# RomeBoardV1.net
KiCad netlist of a schematic drawn in EAGLE
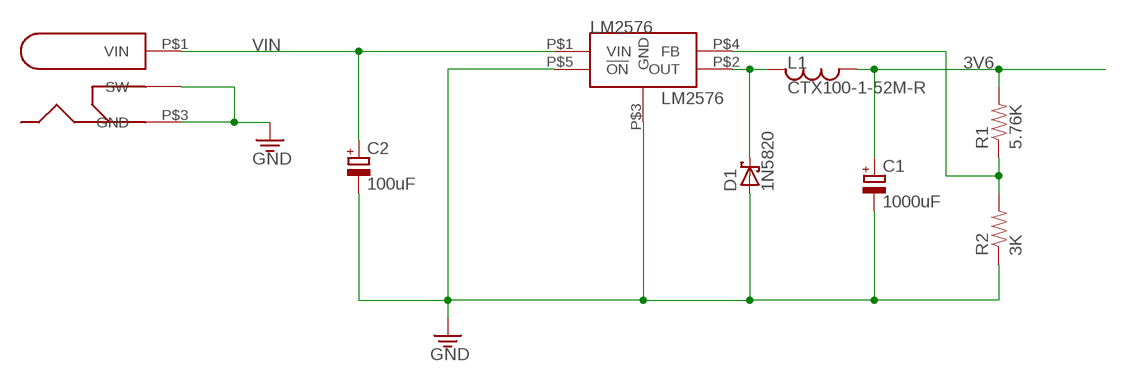
[diagram p0: schematic, sheet 1]
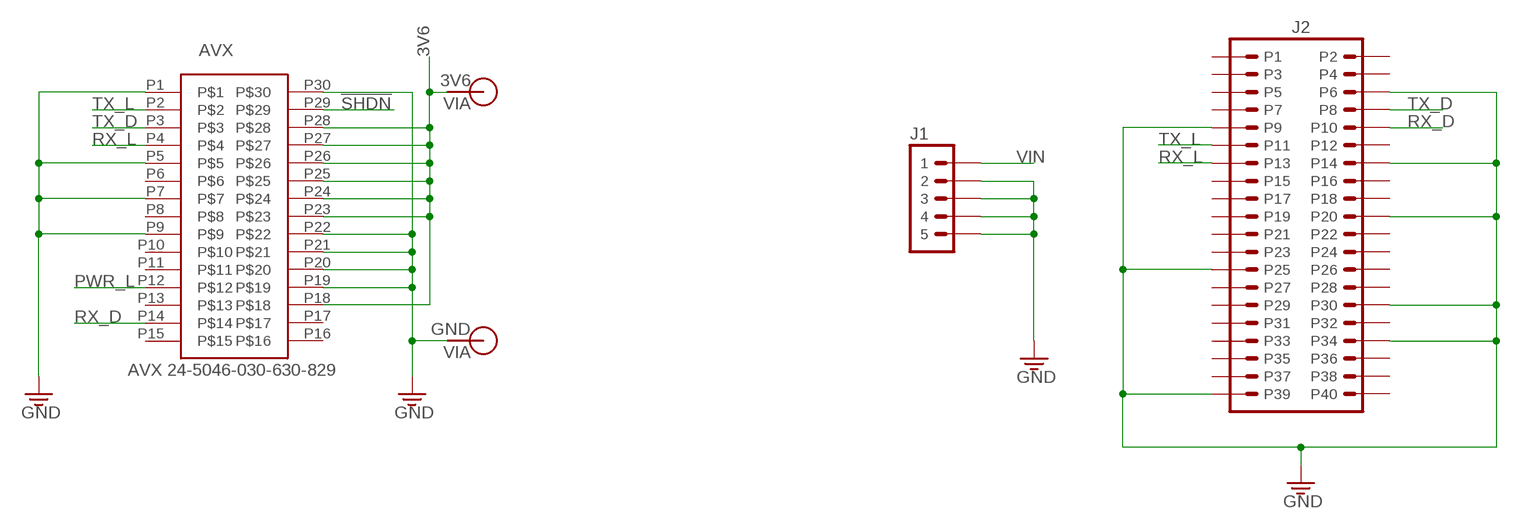
[diagram p1: schematic, sheet 2]
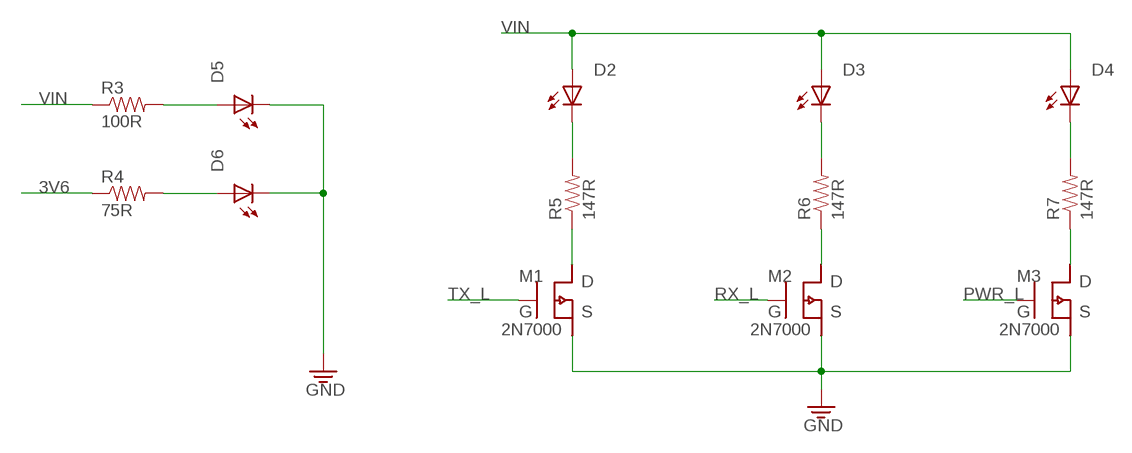
[diagram p2: schematic, sheet 3]

(export (version "E")
  (design (tool "Eeschema 10.0.6"))
  (components
    (comp (ref "AVX")
      (value "AVX-24-5046-030-630-829")
      (footprint "eagle-import:AVX-24-5046-630-829")
      (libsource (lib "eagle-import") (part "AVX-24-5046-030-630-829"))
    )
    (comp (ref "J1")
      (value "HEADER-5")
      (footprint "eagle-import:HEADER-05")
      (libsource (lib "eagle-import") (part "HEADER-5"))
    )
    (comp (ref "J2")
      (value "RASPBERRY-PI-HEADER")
      (footprint "eagle-import:HEADER-20X02")
      (libsource (lib "eagle-import") (part "RASPBERRY-PI-HEADER"))
    )
    (comp (ref "V4")
      (value "GND")
      (footprint "eagle-import:VIA-120MIL")
      (libsource (lib "eagle-import") (part "VIA-120MIL"))
    )
    (comp (ref "V5")
      (value "3V6")
      (footprint "eagle-import:VIA-120MIL")
      (libsource (lib "eagle-import") (part "VIA-120MIL"))
    )
    (comp (ref "D2")
      (value "LEDTHRU-HOLE-CONNECTOR")
      (footprint "eagle-import:1X2-POL")
      (libsource (lib "eagle-import") (part "LEDTHRU-HOLE-CONNECTOR"))
    )
    (comp (ref "D3")
      (value "LEDTHRU-HOLE-CONNECTOR")
      (footprint "eagle-import:1X2-POL")
      (libsource (lib "eagle-import") (part "LEDTHRU-HOLE-CONNECTOR"))
    )
    (comp (ref "D4")
      (value "LEDTHRU-HOLE-CONNECTOR")
      (footprint "eagle-import:1X2-POL")
      (libsource (lib "eagle-import") (part "LEDTHRU-HOLE-CONNECTOR"))
    )
    (comp (ref "D5")
      (value "LEDTHRU-HOLE-CONNECTOR")
      (footprint "eagle-import:1X2-POL")
      (libsource (lib "eagle-import") (part "LEDTHRU-HOLE-CONNECTOR"))
    )
    (comp (ref "D6")
      (value "LEDTHRU-HOLE-CONNECTOR")
      (footprint "eagle-import:1X2-POL")
      (libsource (lib "eagle-import") (part "LEDTHRU-HOLE-CONNECTOR"))
    )
    (comp (ref "M1")
      (value "2N7000")
      (footprint "eagle-import:TO-923-MOS")
      (libsource (lib "eagle-import") (part "2N7000"))
    )
    (comp (ref "M2")
      (value "2N7000")
      (footprint "eagle-import:TO-923-MOS")
      (libsource (lib "eagle-import") (part "2N7000"))
    )
    (comp (ref "M3")
      (value "2N7000")
      (footprint "eagle-import:TO-923-MOS")
      (libsource (lib "eagle-import") (part "2N7000"))
    )
    (comp (ref "R3")
      (value "100R")
      (footprint "eagle-import:AXIAL-0.4")
      (libsource (lib "eagle-import") (part "RESISTOR-PTH0.4"))
    )
    (comp (ref "R4")
      (value "75R")
      (footprint "eagle-import:AXIAL-0.4")
      (libsource (lib "eagle-import") (part "RESISTOR-PTH0.4"))
    )
    (comp (ref "R5")
      (value "147R")
      (footprint "eagle-import:AXIAL-0.4")
      (libsource (lib "eagle-import") (part "RESISTOR-PTH0.4"))
    )
    (comp (ref "R6")
      (value "147R")
      (footprint "eagle-import:AXIAL-0.4")
      (libsource (lib "eagle-import") (part "RESISTOR-PTH0.4"))
    )
    (comp (ref "R7")
      (value "147R")
      (footprint "eagle-import:AXIAL-0.4")
      (libsource (lib "eagle-import") (part "RESISTOR-PTH0.4"))
    )
    (comp (ref "C1")
      (value "1000uF")
      (footprint "eagle-import:E7,5-16")
      (libsource (lib "eagle-import") (part "CPOL-EUE7.5-16"))
    )
    (comp (ref "C2")
      (value "100uF")
      (footprint "eagle-import:E3,5-10")
      (libsource (lib "eagle-import") (part "CPOL-EUE3.5-10"))
    )
    (comp (ref "D1")
      (value "1N5820")
      (footprint "eagle-import:DO-201AD")
      (libsource (lib "eagle-import") (part "1N5820"))
    )
    (comp (ref "L1")
      (value "CTX100-1-52M-R")
      (footprint "eagle-import:CTX100-1-52M-R")
      (libsource (lib "eagle-import") (part "CTX100-1-52M-R"))
    )
    (comp (ref "LM2576")
      (value "LM2576")
      (footprint "eagle-import:TO-220-5")
      (libsource (lib "eagle-import") (part "LM2576"))
    )
    (comp (ref "R1")
      (value "5.76K")
      (footprint "eagle-import:AXIAL-0.4")
      (libsource (lib "eagle-import") (part "RESISTOR-PTH0.4"))
    )
    (comp (ref "R2")
      (value "3K")
      (footprint "eagle-import:AXIAL-0.4")
      (libsource (lib "eagle-import") (part "RESISTOR-PTH0.4"))
    )
    (comp (ref "U$2")
      (value "PJ-002A")
      (footprint "eagle-import:PJ-002A")
      (libsource (lib "eagle-import") (part "PJ-002A"))
    )
  )
  (nets
    (net (code "1") (name "3V6") (class "Default")
      (node (ref "AVX") (pin "P18") (pinfunction "P$18_P18") (pintype "bidirectional"))
      (node (ref "AVX") (pin "P23") (pinfunction "P$23_P23") (pintype "bidirectional"))
      (node (ref "AVX") (pin "P24") (pinfunction "P$24_P24") (pintype "bidirectional"))
      (node (ref "AVX") (pin "P25") (pinfunction "P$25_P25") (pintype "bidirectional"))
      (node (ref "AVX") (pin "P26") (pinfunction "P$26_P26") (pintype "bidirectional"))
      (node (ref "AVX") (pin "P27") (pinfunction "P$27_P27") (pintype "bidirectional"))
      (node (ref "AVX") (pin "P28") (pinfunction "P$28_P28") (pintype "bidirectional"))
      (node (ref "C1") (pin "+") (pinfunction "+_+") (pintype "passive"))
      (node (ref "L1") (pin "P$3") (pinfunction "P$2_P$3") (pintype "passive"))
      (node (ref "R1") (pin "2") (pinfunction "2_2") (pintype "passive"))
      (node (ref "R4") (pin "1") (pinfunction "1_1") (pintype "passive"))
      (node (ref "V5") (pin "P$1") (pinfunction "P$1_P$1") (pintype "bidirectional"))
    )
    (net (code "2") (name "GND") (class "Default")
      (node (ref "AVX") (pin "P1") (pinfunction "P$1_P1") (pintype "bidirectional"))
      (node (ref "AVX") (pin "P19") (pinfunction "P$19_P19") (pintype "bidirectional"))
      (node (ref "AVX") (pin "P20") (pinfunction "P$20_P20") (pintype "bidirectional"))
      (node (ref "AVX") (pin "P21") (pinfunction "P$21_P21") (pintype "bidirectional"))
      (node (ref "AVX") (pin "P22") (pinfunction "P$22_P22") (pintype "bidirectional"))
      (node (ref "AVX") (pin "P30") (pinfunction "P$30_P30") (pintype "bidirectional"))
      (node (ref "AVX") (pin "P5") (pinfunction "P$5_P5") (pintype "bidirectional"))
      (node (ref "AVX") (pin "P7") (pinfunction "P$7_P7") (pintype "bidirectional"))
      (node (ref "AVX") (pin "P9") (pinfunction "P$9_P9") (pintype "bidirectional"))
      (node (ref "C1") (pin "-") (pinfunction "-_-") (pintype "passive"))
      (node (ref "C2") (pin "-") (pinfunction "-_-") (pintype "passive"))
      (node (ref "D1") (pin "P$1") (pinfunction "A_P$1") (pintype "passive"))
      (node (ref "D5") (pin "2") (pinfunction "C_2") (pintype "passive"))
      (node (ref "D6") (pin "2") (pinfunction "C_2") (pintype "passive"))
      (node (ref "J1") (pin "2") (pinfunction "2_2") (pintype "passive"))
      (node (ref "J1") (pin "3") (pinfunction "3_3") (pintype "passive"))
      (node (ref "J1") (pin "4") (pinfunction "4_4") (pintype "passive"))
      (node (ref "J1") (pin "5") (pinfunction "5_5") (pintype "passive"))
      (node (ref "J2") (pin "P14") (pinfunction "P14_P14") (pintype "passive"))
      (node (ref "J2") (pin "P20") (pinfunction "P20_P20") (pintype "passive"))
      (node (ref "J2") (pin "P25") (pinfunction "P25_P25") (pintype "passive"))
      (node (ref "J2") (pin "P30") (pinfunction "P30_P30") (pintype "passive"))
      (node (ref "J2") (pin "P34") (pinfunction "P34_P34") (pintype "passive"))
      (node (ref "J2") (pin "P39") (pinfunction "P39_P39") (pintype "passive"))
      (node (ref "J2") (pin "P6") (pinfunction "P6_P6") (pintype "passive"))
      (node (ref "J2") (pin "P9") (pinfunction "P9_P9") (pintype "passive"))
      (node (ref "LM2576") (pin "P$3") (pinfunction "GND_P$3") (pintype "bidirectional"))
      (node (ref "LM2576") (pin "P$5") (pinfunction "~{ON}_P$5") (pintype "bidirectional"))
      (node (ref "M1") (pin "3") (pinfunction "S_3") (pintype "bidirectional"))
      (node (ref "M2") (pin "3") (pinfunction "S_3") (pintype "bidirectional"))
      (node (ref "M3") (pin "3") (pinfunction "S_3") (pintype "bidirectional"))
      (node (ref "R2") (pin "1") (pinfunction "1_1") (pintype "passive"))
      (node (ref "U$2") (pin "P$2") (pinfunction "SW_P$2") (pintype "bidirectional"))
      (node (ref "U$2") (pin "P$3") (pinfunction "GND_P$3") (pintype "bidirectional"))
      (node (ref "V4") (pin "P$1") (pinfunction "P$1_P$1") (pintype "bidirectional"))
    )
    (net (code "3") (name "Net-(D1-C)") (class "Default")
      (node (ref "D1") (pin "P$2") (pinfunction "C_P$2") (pintype "passive"))
      (node (ref "L1") (pin "P$1") (pinfunction "P$1_P$1") (pintype "passive"))
      (node (ref "LM2576") (pin "P$2") (pinfunction "OUT_P$2") (pintype "bidirectional"))
    )
    (net (code "4") (name "Net-(D2-C)") (class "Default")
      (node (ref "D2") (pin "2") (pinfunction "C_2") (pintype "passive"))
      (node (ref "R5") (pin "2") (pinfunction "2_2") (pintype "passive"))
    )
    (net (code "5") (name "Net-(D3-C)") (class "Default")
      (node (ref "D3") (pin "2") (pinfunction "C_2") (pintype "passive"))
      (node (ref "R6") (pin "2") (pinfunction "2_2") (pintype "passive"))
    )
    (net (code "6") (name "Net-(D4-C)") (class "Default")
      (node (ref "D4") (pin "2") (pinfunction "C_2") (pintype "passive"))
      (node (ref "R7") (pin "2") (pinfunction "2_2") (pintype "passive"))
    )
    (net (code "7") (name "Net-(D5-A)") (class "Default")
      (node (ref "D5") (pin "1") (pinfunction "A_1") (pintype "passive"))
      (node (ref "R3") (pin "2") (pinfunction "2_2") (pintype "passive"))
    )
    (net (code "8") (name "Net-(D6-A)") (class "Default")
      (node (ref "D6") (pin "1") (pinfunction "A_1") (pintype "passive"))
      (node (ref "R4") (pin "2") (pinfunction "2_2") (pintype "passive"))
    )
    (net (code "9") (name "Net-(LM2576-FB)") (class "Default")
      (node (ref "LM2576") (pin "P$4") (pinfunction "FB_P$4") (pintype "bidirectional"))
      (node (ref "R1") (pin "1") (pinfunction "1_1") (pintype "passive"))
      (node (ref "R2") (pin "2") (pinfunction "2_2") (pintype "passive"))
    )
    (net (code "10") (name "Net-(M1-D)") (class "Default")
      (node (ref "M1") (pin "1") (pinfunction "D_1") (pintype "bidirectional"))
      (node (ref "R5") (pin "1") (pinfunction "1_1") (pintype "passive"))
    )
    (net (code "11") (name "Net-(M2-D)") (class "Default")
      (node (ref "M2") (pin "1") (pinfunction "D_1") (pintype "bidirectional"))
      (node (ref "R6") (pin "1") (pinfunction "1_1") (pintype "passive"))
    )
    (net (code "12") (name "Net-(M3-D)") (class "Default")
      (node (ref "M3") (pin "1") (pinfunction "D_1") (pintype "bidirectional"))
      (node (ref "R7") (pin "1") (pinfunction "1_1") (pintype "passive"))
    )
    (net (code "13") (name "PWR_L") (class "Default")
      (node (ref "AVX") (pin "P12") (pinfunction "P$12_P12") (pintype "bidirectional"))
      (node (ref "M3") (pin "2") (pinfunction "G_2") (pintype "bidirectional"))
    )
    (net (code "14") (name "RX_D") (class "Default")
      (node (ref "AVX") (pin "P14") (pinfunction "P$14_P14") (pintype "bidirectional"))
      (node (ref "J2") (pin "P10") (pinfunction "P10_P10") (pintype "passive"))
    )
    (net (code "15") (name "RX_L") (class "Default")
      (node (ref "AVX") (pin "P4") (pinfunction "P$4_P4") (pintype "bidirectional"))
      (node (ref "J2") (pin "P13") (pinfunction "P13_P13") (pintype "passive"))
      (node (ref "M2") (pin "2") (pinfunction "G_2") (pintype "bidirectional"))
    )
    (net (code "16") (name "TX_D") (class "Default")
      (node (ref "AVX") (pin "P3") (pinfunction "P$3_P3") (pintype "bidirectional"))
      (node (ref "J2") (pin "P8") (pinfunction "P8_P8") (pintype "passive"))
    )
    (net (code "17") (name "TX_L") (class "Default")
      (node (ref "AVX") (pin "P2") (pinfunction "P$2_P2") (pintype "bidirectional"))
      (node (ref "J2") (pin "P11") (pinfunction "P11_P11") (pintype "passive"))
      (node (ref "M1") (pin "2") (pinfunction "G_2") (pintype "bidirectional"))
    )
    (net (code "18") (name "VIN") (class "Default")
      (node (ref "C2") (pin "+") (pinfunction "+_+") (pintype "passive"))
      (node (ref "D2") (pin "1") (pinfunction "A_1") (pintype "passive"))
      (node (ref "D3") (pin "1") (pinfunction "A_1") (pintype "passive"))
      (node (ref "D4") (pin "1") (pinfunction "A_1") (pintype "passive"))
      (node (ref "J1") (pin "1") (pinfunction "1_1") (pintype "passive"))
      (node (ref "LM2576") (pin "P$1") (pinfunction "VIN_P$1") (pintype "bidirectional"))
      (node (ref "R3") (pin "1") (pinfunction "1_1") (pintype "passive"))
      (node (ref "U$2") (pin "P$1") (pinfunction "VIN_P$1") (pintype "bidirectional"))
    )
    (net (code "19") (name "unconnected-(AVX-P$6-PadP6)") (class "Default")
      (node (ref "AVX") (pin "P6") (pinfunction "P$6_P6") (pintype "bidirectional"))
    )
    (net (code "20") (name "unconnected-(AVX-P$8-PadP8)") (class "Default")
      (node (ref "AVX") (pin "P8") (pinfunction "P$8_P8") (pintype "bidirectional"))
    )
    (net (code "21") (name "unconnected-(AVX-P$10-PadP10)") (class "Default")
      (node (ref "AVX") (pin "P10") (pinfunction "P$10_P10") (pintype "bidirectional"))
    )
    (net (code "22") (name "unconnected-(AVX-P$11-PadP11)") (class "Default")
      (node (ref "AVX") (pin "P11") (pinfunction "P$11_P11") (pintype "bidirectional"))
    )
    (net (code "23") (name "unconnected-(AVX-P$13-PadP13)") (class "Default")
      (node (ref "AVX") (pin "P13") (pinfunction "P$13_P13") (pintype "bidirectional"))
    )
    (net (code "24") (name "unconnected-(AVX-P$15-PadP15)") (class "Default")
      (node (ref "AVX") (pin "P15") (pinfunction "P$15_P15") (pintype "bidirectional"))
    )
    (net (code "25") (name "unconnected-(AVX-P$16-PadP16)") (class "Default")
      (node (ref "AVX") (pin "P16") (pinfunction "P$16_P16") (pintype "bidirectional"))
    )
    (net (code "26") (name "unconnected-(AVX-P$17-PadP17)") (class "Default")
      (node (ref "AVX") (pin "P17") (pinfunction "P$17_P17") (pintype "bidirectional"))
    )
    (net (code "27") (name "unconnected-(J2-PadP1)") (class "Default")
      (node (ref "J2") (pin "P1") (pinfunction "P1_P1") (pintype "passive"))
    )
    (net (code "28") (name "unconnected-(J2-PadP2)") (class "Default")
      (node (ref "J2") (pin "P2") (pinfunction "P2_P2") (pintype "passive"))
    )
    (net (code "29") (name "unconnected-(J2-PadP3)") (class "Default")
      (node (ref "J2") (pin "P3") (pinfunction "P3_P3") (pintype "passive"))
    )
    (net (code "30") (name "unconnected-(J2-PadP4)") (class "Default")
      (node (ref "J2") (pin "P4") (pinfunction "P4_P4") (pintype "passive"))
    )
    (net (code "31") (name "unconnected-(J2-PadP5)") (class "Default")
      (node (ref "J2") (pin "P5") (pinfunction "P5_P5") (pintype "passive"))
    )
    (net (code "32") (name "unconnected-(J2-PadP7)") (class "Default")
      (node (ref "J2") (pin "P7") (pinfunction "P7_P7") (pintype "passive"))
    )
    (net (code "33") (name "unconnected-(J2-PadP12)") (class "Default")
      (node (ref "J2") (pin "P12") (pinfunction "P12_P12") (pintype "passive"))
    )
    (net (code "34") (name "unconnected-(J2-PadP15)") (class "Default")
      (node (ref "J2") (pin "P15") (pinfunction "P15_P15") (pintype "passive"))
    )
    (net (code "35") (name "unconnected-(J2-PadP16)") (class "Default")
      (node (ref "J2") (pin "P16") (pinfunction "P16_P16") (pintype "passive"))
    )
    (net (code "36") (name "unconnected-(J2-PadP17)") (class "Default")
      (node (ref "J2") (pin "P17") (pinfunction "P17_P17") (pintype "passive"))
    )
    (net (code "37") (name "unconnected-(J2-PadP18)") (class "Default")
      (node (ref "J2") (pin "P18") (pinfunction "P18_P18") (pintype "passive"))
    )
    (net (code "38") (name "unconnected-(J2-PadP19)") (class "Default")
      (node (ref "J2") (pin "P19") (pinfunction "P19_P19") (pintype "passive"))
    )
    (net (code "39") (name "unconnected-(J2-PadP21)") (class "Default")
      (node (ref "J2") (pin "P21") (pinfunction "P21_P21") (pintype "passive"))
    )
    (net (code "40") (name "unconnected-(J2-PadP22)") (class "Default")
      (node (ref "J2") (pin "P22") (pinfunction "P22_P22") (pintype "passive"))
    )
    (net (code "41") (name "unconnected-(J2-PadP23)") (class "Default")
      (node (ref "J2") (pin "P23") (pinfunction "P23_P23") (pintype "passive"))
    )
    (net (code "42") (name "unconnected-(J2-PadP24)") (class "Default")
      (node (ref "J2") (pin "P24") (pinfunction "P24_P24") (pintype "passive"))
    )
    (net (code "43") (name "unconnected-(J2-PadP26)") (class "Default")
      (node (ref "J2") (pin "P26") (pinfunction "P26_P26") (pintype "passive"))
    )
    (net (code "44") (name "unconnected-(J2-PadP27)") (class "Default")
      (node (ref "J2") (pin "P27") (pinfunction "P27_P27") (pintype "passive"))
    )
    (net (code "45") (name "unconnected-(J2-PadP28)") (class "Default")
      (node (ref "J2") (pin "P28") (pinfunction "P28_P28") (pintype "passive"))
    )
    (net (code "46") (name "unconnected-(J2-PadP29)") (class "Default")
      (node (ref "J2") (pin "P29") (pinfunction "P29_P29") (pintype "passive"))
    )
    (net (code "47") (name "unconnected-(J2-PadP31)") (class "Default")
      (node (ref "J2") (pin "P31") (pinfunction "P31_P31") (pintype "passive"))
    )
    (net (code "48") (name "unconnected-(J2-PadP32)") (class "Default")
      (node (ref "J2") (pin "P32") (pinfunction "P32_P32") (pintype "passive"))
    )
    (net (code "49") (name "unconnected-(J2-PadP33)") (class "Default")
      (node (ref "J2") (pin "P33") (pinfunction "P33_P33") (pintype "passive"))
    )
    (net (code "50") (name "unconnected-(J2-PadP35)") (class "Default")
      (node (ref "J2") (pin "P35") (pinfunction "P35_P35") (pintype "passive"))
    )
    (net (code "51") (name "unconnected-(J2-PadP36)") (class "Default")
      (node (ref "J2") (pin "P36") (pinfunction "P36_P36") (pintype "passive"))
    )
    (net (code "52") (name "unconnected-(J2-PadP37)") (class "Default")
      (node (ref "J2") (pin "P37") (pinfunction "P37_P37") (pintype "passive"))
    )
    (net (code "53") (name "unconnected-(J2-PadP38)") (class "Default")
      (node (ref "J2") (pin "P38") (pinfunction "P38_P38") (pintype "passive"))
    )
    (net (code "54") (name "unconnected-(J2-PadP40)") (class "Default")
      (node (ref "J2") (pin "P40") (pinfunction "P40_P40") (pintype "passive"))
    )
    (net (code "55") (name "~{SHDN}") (class "Default")
      (node (ref "AVX") (pin "P29") (pinfunction "P$29_P29") (pintype "bidirectional"))
    )
  )
)
